# Controller.net
KiCad netlist of a schematic drawn in Altium Designer
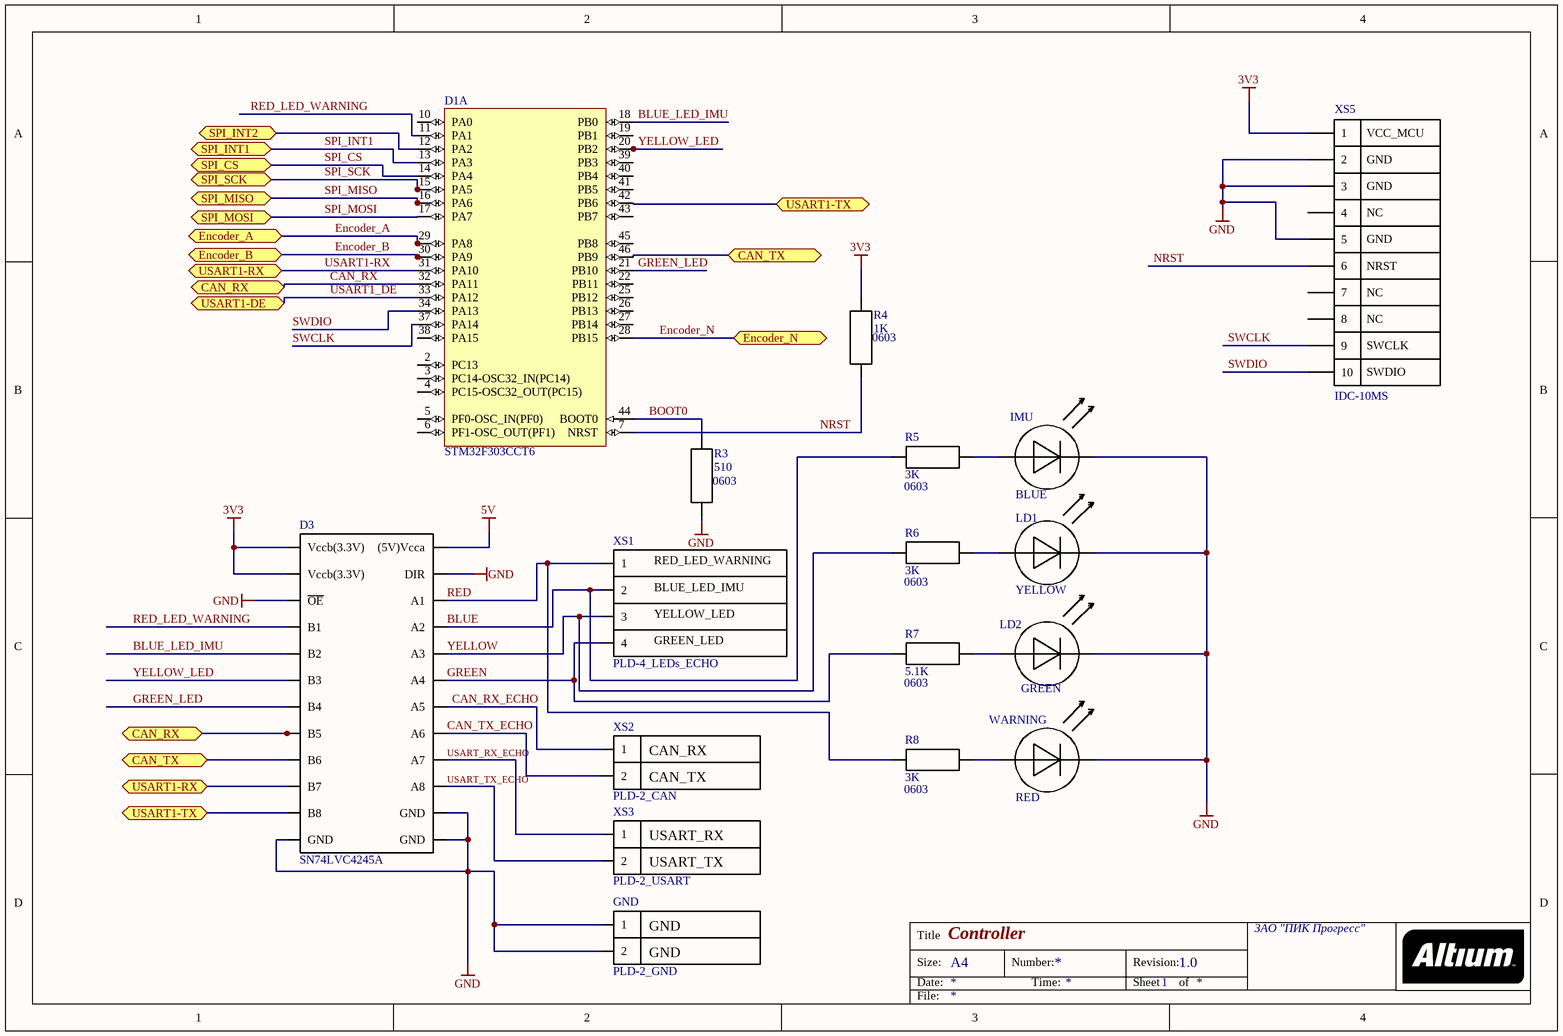
[diagram p0: Controller.SchDoc]

(export (version "E")
  (design (tool "Eeschema 10.0.6"))
  (components
    (comp (ref "D1")
      (value "STM32F303CCT6")
      (footprint "STM-LQFP48_N")
      (libsource (lib "STMicroelectronics STM32 F3") (part "STM32F303CCT6"))
    )
    (comp (ref "D3")
      (value "SN74LVC4245A")
      (footprint "Mylibrary:SOIC_24_DW(R-PDSO-G24)")
      (description "optic bus transiever with 3-state")
      (libsource (lib "Mylibrary") (part "SN74LVC4245A"))
    )
    (comp (ref "GND")
      (value "PLD-2_GND")
      (footprint "Mylibrary:PLS_2_simple")
      (libsource (lib "Mylibrary") (part "PLD-2_GND"))
    )
    (comp (ref "IMU")
      (value "BLUE")
      (footprint "Mylibrary:SMD_LED_3216")
      (libsource (lib "Mylibrary") (part "LED_Diode"))
    )
    (comp (ref "LD1")
      (value "YELLOW")
      (footprint "Mylibrary:SMD_LED")
      (libsource (lib "Mylibrary") (part "LED_Diode"))
    )
    (comp (ref "LD2")
      (value "GREEN")
      (footprint "Mylibrary:SMD_LED")
      (libsource (lib "Mylibrary") (part "LED_Diode"))
    )
    (comp (ref "R3") (value "510") (footprint "SMD_0603") (libsource (lib "Mylibrary") (part "Resistor")))
    (comp (ref "R4") (value "1K") (footprint "SMD_0603") (libsource (lib "Mylibrary") (part "Resistor")))
    (comp (ref "R5") (value "3K") (footprint "SMD_0603") (libsource (lib "Mylibrary") (part "Resistor")))
    (comp (ref "R6") (value "3K") (footprint "SMD_0603") (libsource (lib "Mylibrary") (part "Resistor")))
    (comp (ref "R7") (value "5.1K") (footprint "SMD_0603") (libsource (lib "Mylibrary") (part "Resistor")))
    (comp (ref "R8") (value "3K") (footprint "SMD_0603") (libsource (lib "Mylibrary") (part "Resistor")))
    (comp (ref "WARNING")
      (value "RED")
      (footprint "Mylibrary:SMD_LED")
      (libsource (lib "Mylibrary") (part "LED_Diode"))
    )
    (comp (ref "XS1")
      (value "PLD-4_LEDs_ECHO")
      (footprint "Mylibrary:PLS_4")
      (libsource (lib "Mylibrary") (part "PLD-4_LEDs_ECHO"))
    )
    (comp (ref "XS2")
      (value "PLD-2_CAN")
      (footprint "Mylibrary:PLS_2_simple")
      (libsource (lib "Mylibrary") (part "PLD-2_CAN"))
    )
    (comp (ref "XS3")
      (value "PLD-2_USART")
      (footprint "Mylibrary:PLS_2_simple")
      (libsource (lib "Mylibrary") (part "PLD-2_USART"))
    )
    (comp (ref "XS5")
      (value "IDC-10MS")
      (footprint "Connectors_SMD:IDC-10MS")
      (libsource (lib "Connectors") (part "IDC-10MS"))
    )
  )
  (nets
    (net (code "1") (name "/BLUE") (class "Default")
      (node (ref "D3") (pin "4") (pinfunction "A2_4") (pintype "passive"))
      (node (ref "R5") (pin "1") (pinfunction "1_1") (pintype "passive"))
      (node (ref "XS1") (pin "2") (pinfunction "2_2") (pintype "passive"))
    )
    (net (code "2") (name "/BLUE_LED_IMU") (class "Default")
      (node (ref "D1") (pin "18") (pinfunction "PB0_18") (pintype "bidirectional"))
      (node (ref "D3") (pin "20") (pinfunction "B2_20") (pintype "passive"))
    )
    (net (code "3") (name "/BOOT0") (class "Default")
      (node (ref "D1") (pin "44") (pinfunction "BOOT0_44") (pintype "input"))
      (node (ref "R3") (pin "2") (pinfunction "2_2") (pintype "passive"))
    )
    (net (code "4") (name "/CAN_RX") (class "Default")
      (node (ref "D1") (pin "32") (pinfunction "PA11_32") (pintype "bidirectional"))
      (node (ref "D3") (pin "17") (pinfunction "B5_17") (pintype "passive"))
    )
    (net (code "5") (name "/CAN_RX_ECHO") (class "Default")
      (node (ref "D3") (pin "7") (pinfunction "A5_7") (pintype "passive"))
      (node (ref "XS2") (pin "1") (pinfunction "1_1") (pintype "passive"))
    )
    (net (code "6") (name "/CAN_TX") (class "Default")
      (node (ref "D1") (pin "46") (pinfunction "PB9_46") (pintype "bidirectional"))
      (node (ref "D3") (pin "16") (pinfunction "B6_16") (pintype "passive"))
    )
    (net (code "7") (name "/CAN_TX_ECHO") (class "Default")
      (node (ref "D3") (pin "8") (pinfunction "A6_8") (pintype "passive"))
      (node (ref "XS2") (pin "2") (pinfunction "2_2") (pintype "passive"))
    )
    (net (code "8") (name "/Encoder_A") (class "Default")
      (node (ref "D1") (pin "29") (pinfunction "PA8_29") (pintype "bidirectional"))
    )
    (net (code "9") (name "/Encoder_B") (class "Default")
      (node (ref "D1") (pin "30") (pinfunction "PA9_30") (pintype "bidirectional"))
    )
    (net (code "10") (name "/Encoder_N") (class "Default")
      (node (ref "D1") (pin "28") (pinfunction "PB15_28") (pintype "bidirectional"))
    )
    (net (code "11") (name "/GREEN") (class "Default")
      (node (ref "D3") (pin "6") (pinfunction "A4_6") (pintype "passive"))
      (node (ref "R7") (pin "1") (pinfunction "1_1") (pintype "passive"))
      (node (ref "XS1") (pin "4") (pinfunction "4_4") (pintype "passive"))
    )
    (net (code "12") (name "/GREEN_LED") (class "Default")
      (node (ref "D1") (pin "21") (pinfunction "PB10_21") (pintype "bidirectional"))
      (node (ref "D3") (pin "18") (pinfunction "B4_18") (pintype "passive"))
    )
    (net (code "13") (name "/NRST") (class "Default")
      (node (ref "D1") (pin "7") (pinfunction "NRST_7") (pintype "bidirectional"))
      (node (ref "R4") (pin "1") (pinfunction "1_1") (pintype "passive"))
      (node (ref "XS5") (pin "6") (pinfunction "6_6") (pintype "passive"))
    )
    (net (code "14") (name "/RED") (class "Default")
      (node (ref "D3") (pin "3") (pinfunction "A1_3") (pintype "passive"))
      (node (ref "R8") (pin "1") (pinfunction "1_1") (pintype "passive"))
      (node (ref "XS1") (pin "1") (pinfunction "1_1") (pintype "passive"))
    )
    (net (code "15") (name "/RED_LED_WARNING") (class "Default")
      (node (ref "D1") (pin "11") (pinfunction "PA1_11") (pintype "bidirectional"))
      (node (ref "D3") (pin "21") (pinfunction "B1_21") (pintype "passive"))
    )
    (net (code "16") (name "/SPI_CS") (class "Default")
      (node (ref "D1") (pin "14") (pinfunction "PA4_14") (pintype "bidirectional"))
    )
    (net (code "17") (name "/SPI_INT1") (class "Default")
      (node (ref "D1") (pin "13") (pinfunction "PA3_13") (pintype "bidirectional"))
    )
    (net (code "18") (name "/SPI_INT2") (class "Default")
      (node (ref "D1") (pin "12") (pinfunction "PA2_12") (pintype "bidirectional"))
    )
    (net (code "19") (name "/SPI_MISO") (class "Default")
      (node (ref "D1") (pin "16") (pinfunction "PA6_16") (pintype "bidirectional"))
    )
    (net (code "20") (name "/SPI_MOSI") (class "Default")
      (node (ref "D1") (pin "17") (pinfunction "PA7_17") (pintype "bidirectional"))
    )
    (net (code "21") (name "/SPI_SCK") (class "Default")
      (node (ref "D1") (pin "15") (pinfunction "PA5_15") (pintype "bidirectional"))
    )
    (net (code "22") (name "/SWCLK") (class "Default")
      (node (ref "D1") (pin "37") (pinfunction "PA14_37") (pintype "bidirectional"))
      (node (ref "XS5") (pin "9") (pinfunction "9_9") (pintype "passive"))
    )
    (net (code "23") (name "/SWDIO") (class "Default")
      (node (ref "D1") (pin "34") (pinfunction "PA13_34") (pintype "bidirectional"))
      (node (ref "XS5") (pin "10") (pinfunction "10_10") (pintype "passive"))
    )
    (net (code "24") (name "/USART1-RX") (class "Default")
      (node (ref "D1") (pin "31") (pinfunction "PA10_31") (pintype "bidirectional"))
      (node (ref "D3") (pin "15") (pinfunction "B7_15") (pintype "passive"))
    )
    (net (code "25") (name "/USART1-TX") (class "Default")
      (node (ref "D1") (pin "42") (pinfunction "PB6_42") (pintype "bidirectional"))
      (node (ref "D3") (pin "14") (pinfunction "B8_14") (pintype "passive"))
    )
    (net (code "26") (name "/USART1_DE") (class "Default")
      (node (ref "D1") (pin "33") (pinfunction "PA12_33") (pintype "bidirectional"))
    )
    (net (code "27") (name "/USART_RX_ECHO") (class "Default")
      (node (ref "D3") (pin "9") (pinfunction "A7_9") (pintype "passive"))
      (node (ref "XS3") (pin "1") (pinfunction "1_1") (pintype "passive"))
    )
    (net (code "28") (name "/USART_TX_ECHO") (class "Default")
      (node (ref "D3") (pin "10") (pinfunction "A8_10") (pintype "passive"))
      (node (ref "XS3") (pin "2") (pinfunction "2_2") (pintype "passive"))
    )
    (net (code "29") (name "/YELLOW") (class "Default")
      (node (ref "D3") (pin "5") (pinfunction "A3_5") (pintype "passive"))
      (node (ref "R6") (pin "1") (pinfunction "1_1") (pintype "passive"))
      (node (ref "XS1") (pin "3") (pinfunction "3_3") (pintype "passive"))
    )
    (net (code "30") (name "/YELLOW_LED") (class "Default")
      (node (ref "D1") (pin "20") (pinfunction "PB2_20") (pintype "bidirectional"))
      (node (ref "D3") (pin "19") (pinfunction "B3_19") (pintype "passive"))
    )
    (net (code "31") (name "3V3") (class "Default")
      (node (ref "D3") (pin "23") (pinfunction "Vccb(3.3V)_23") (pintype "passive"))
      (node (ref "D3") (pin "24") (pinfunction "Vccb(3.3V)_24") (pintype "passive"))
      (node (ref "R4") (pin "2") (pinfunction "2_2") (pintype "passive"))
      (node (ref "XS5") (pin "1") (pinfunction "1_1") (pintype "passive"))
    )
    (net (code "32") (name "5V") (class "Default")
      (node (ref "D3") (pin "1") (pinfunction "(5V)Vcca_1") (pintype "passive"))
    )
    (net (code "33") (name "GND") (class "Default")
      (node (ref "D3") (pin "11") (pinfunction "GND_11") (pintype "passive"))
      (node (ref "D3") (pin "12") (pinfunction "GND_12") (pintype "passive"))
      (node (ref "D3") (pin "13") (pinfunction "GND_13") (pintype "passive"))
      (node (ref "D3") (pin "2") (pinfunction "DIR_2") (pintype "passive"))
      (node (ref "D3") (pin "22") (pinfunction "~{OE}_22") (pintype "passive"))
      (node (ref "GND") (pin "1") (pinfunction "1_1") (pintype "passive"))
      (node (ref "GND") (pin "2") (pinfunction "2_2") (pintype "passive"))
      (node (ref "IMU") (pin "1") (pintype "passive"))
      (node (ref "LD1") (pin "1") (pintype "passive"))
      (node (ref "LD2") (pin "1") (pintype "passive"))
      (node (ref "R3") (pin "1") (pinfunction "1_1") (pintype "passive"))
      (node (ref "WARNING") (pin "1") (pintype "passive"))
      (node (ref "XS5") (pin "2") (pinfunction "2_2") (pintype "passive"))
      (node (ref "XS5") (pin "3") (pinfunction "3_3") (pintype "passive"))
      (node (ref "XS5") (pin "5") (pinfunction "5_5") (pintype "passive"))
    )
    (net (code "34") (name "Net-(IMU-Pad2)") (class "Default")
      (node (ref "IMU") (pin "2") (pintype "passive"))
      (node (ref "R5") (pin "2") (pinfunction "2_2") (pintype "passive"))
    )
    (net (code "35") (name "Net-(LD1-Pad2)") (class "Default")
      (node (ref "LD1") (pin "2") (pintype "passive"))
      (node (ref "R6") (pin "2") (pinfunction "2_2") (pintype "passive"))
    )
    (net (code "36") (name "Net-(LD2-Pad2)") (class "Default")
      (node (ref "LD2") (pin "2") (pintype "passive"))
      (node (ref "R7") (pin "2") (pinfunction "2_2") (pintype "passive"))
    )
    (net (code "37") (name "Net-(R8-Pad2)") (class "Default")
      (node (ref "R8") (pin "2") (pinfunction "2_2") (pintype "passive"))
      (node (ref "WARNING") (pin "2") (pintype "passive"))
    )
    (net (code "38") (name "unconnected-(D1A-PA0-Pad10)") (class "Default")
      (node (ref "D1") (pin "10") (pinfunction "PA0_10") (pintype "bidirectional"))
    )
    (net (code "39") (name "unconnected-(D1A-PA15-Pad38)") (class "Default")
      (node (ref "D1") (pin "38") (pinfunction "PA15_38") (pintype "bidirectional"))
    )
    (net (code "40") (name "unconnected-(D1A-PB1-Pad19)") (class "Default")
      (node (ref "D1") (pin "19") (pinfunction "PB1_19") (pintype "bidirectional"))
    )
    (net (code "41") (name "unconnected-(D1A-PB3-Pad39)") (class "Default")
      (node (ref "D1") (pin "39") (pinfunction "PB3_39") (pintype "bidirectional"))
    )
    (net (code "42") (name "unconnected-(D1A-PB4-Pad40)") (class "Default")
      (node (ref "D1") (pin "40") (pinfunction "PB4_40") (pintype "bidirectional"))
    )
    (net (code "43") (name "unconnected-(D1A-PB5-Pad41)") (class "Default")
      (node (ref "D1") (pin "41") (pinfunction "PB5_41") (pintype "bidirectional"))
    )
    (net (code "44") (name "unconnected-(D1A-PB7-Pad43)") (class "Default")
      (node (ref "D1") (pin "43") (pinfunction "PB7_43") (pintype "bidirectional"))
    )
    (net (code "45") (name "unconnected-(D1A-PB8-Pad45)") (class "Default")
      (node (ref "D1") (pin "45") (pinfunction "PB8_45") (pintype "bidirectional"))
    )
    (net (code "46") (name "unconnected-(D1A-PB11-Pad22)") (class "Default")
      (node (ref "D1") (pin "22") (pinfunction "PB11_22") (pintype "bidirectional"))
    )
    (net (code "47") (name "unconnected-(D1A-PB12-Pad25)") (class "Default")
      (node (ref "D1") (pin "25") (pinfunction "PB12_25") (pintype "bidirectional"))
    )
    (net (code "48") (name "unconnected-(D1A-PB13-Pad26)") (class "Default")
      (node (ref "D1") (pin "26") (pinfunction "PB13_26") (pintype "bidirectional"))
    )
    (net (code "49") (name "unconnected-(D1A-PB14-Pad27)") (class "Default")
      (node (ref "D1") (pin "27") (pinfunction "PB14_27") (pintype "bidirectional"))
    )
    (net (code "50") (name "unconnected-(D1A-PC13-Pad2)") (class "Default")
      (node (ref "D1") (pin "2") (pinfunction "PC13_2") (pintype "bidirectional"))
    )
    (net (code "51") (name "unconnected-(D1A-PC14-OSC32_IN(PC14)-Pad3)") (class "Default")
      (node (ref "D1") (pin "3") (pinfunction "PC14-OSC32_IN(PC14)_3") (pintype "bidirectional"))
    )
    (net (code "52") (name "unconnected-(D1A-PC15-OSC32_OUT(PC15)-Pad4)") (class "Default")
      (node (ref "D1") (pin "4") (pinfunction "PC15-OSC32_OUT(PC15)_4") (pintype "bidirectional"))
    )
    (net (code "53") (name "unconnected-(D1A-PF0-OSC_IN(PF0)-Pad5)") (class "Default")
      (node (ref "D1") (pin "5") (pinfunction "PF0-OSC_IN(PF0)_5") (pintype "bidirectional"))
    )
    (net (code "54") (name "unconnected-(D1A-PF1-OSC_OUT(PF1)-Pad6)") (class "Default")
      (node (ref "D1") (pin "6") (pinfunction "PF1-OSC_OUT(PF1)_6") (pintype "bidirectional"))
    )
    (net (code "55") (name "unconnected-(XS5-Pad4)") (class "Default")
      (node (ref "XS5") (pin "4") (pinfunction "4_4") (pintype "passive"))
    )
    (net (code "56") (name "unconnected-(XS5-Pad7)") (class "Default")
      (node (ref "XS5") (pin "7") (pinfunction "7_7") (pintype "passive"))
    )
    (net (code "57") (name "unconnected-(XS5-Pad8)") (class "Default")
      (node (ref "XS5") (pin "8") (pinfunction "8_8") (pintype "passive"))
    )
  )
)
